# mcu.net
KiCad netlist of a schematic drawn in Altium Designer
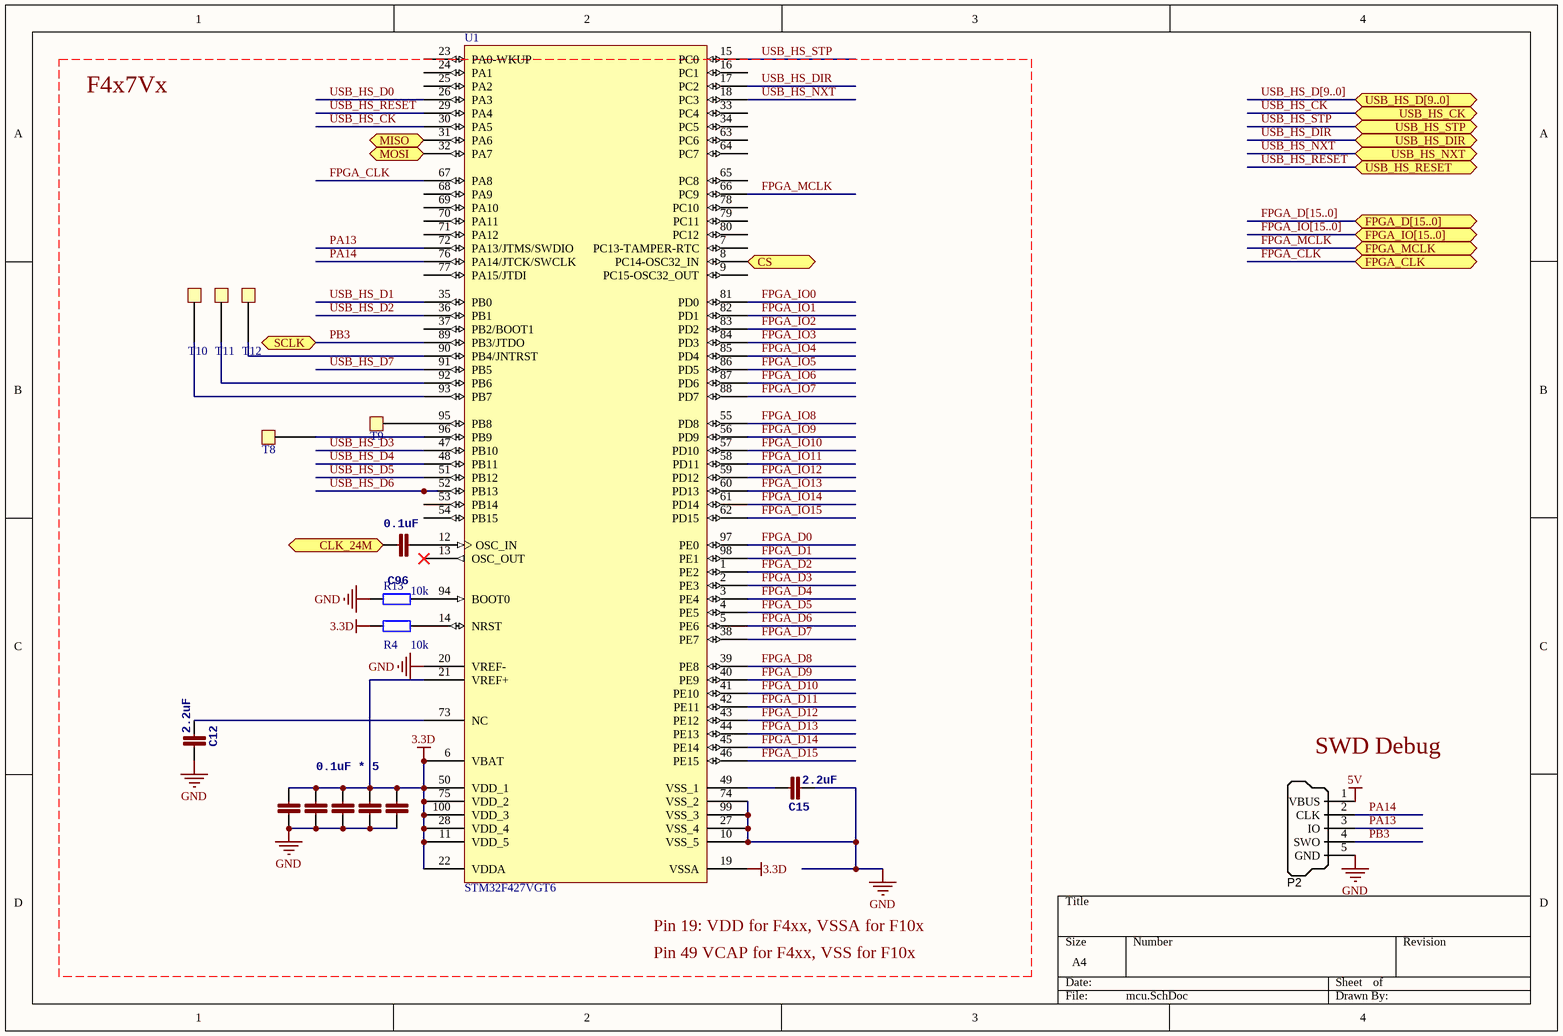
[diagram p0: mcu.SchDoc]

(export (version "E")
  (design (tool "Eeschema 10.0.6"))
  (components
    (comp (ref "C4")
      (value "0.1uF * 5")
      (footprint "0402")
      (description "<b>Capacitor</b>\nStandard 0603 ceramic capacitor, and 0.1\" leaded capacitor.")
      (fields (field (name "PARTNO") "CC0402ZRY5V7BB104"))
      (libsource (lib "*") (part "CAP0402-CAP"))
    )
    (comp (ref "C5")
      (value "1n")
      (footprint "0402")
      (description "<b>Capacitor</b>\nStandard 0603 ceramic capacitor, and 0.1\" leaded capacitor.")
      (fields (field (name "PARTNO") "CC0402ZRY5V7BB104"))
      (libsource (lib "") (part "CAP0402-CAP_1"))
    )
    (comp (ref "C6")
      (value "1n")
      (footprint "0402")
      (description "<b>Capacitor</b>\nStandard 0603 ceramic capacitor, and 0.1\" leaded capacitor.")
      (fields (field (name "PARTNO") "CC0402ZRY5V7BB104"))
      (libsource (lib "") (part "CAP0402-CAP_1"))
    )
    (comp (ref "C12")
      (value "2.2uF")
      (footprint "0603")
      (description "<b>Capacitor</b>\nStandard 0603 ceramic capacitor, and 0.1\" leaded capacitor.")
      (fields (field (name "PARTNO") "CC0402ZRY5V7BB104"))
      (libsource (lib "") (part "CAP0402-CAP_1"))
    )
    (comp (ref "C13")
      (value "1n")
      (footprint "0402")
      (description "<b>Capacitor</b>\nStandard 0603 ceramic capacitor, and 0.1\" leaded capacitor.")
      (fields (field (name "PARTNO") "CC0402ZRY5V7BB104"))
      (libsource (lib "") (part "CAP0402-CAP_1"))
    )
    (comp (ref "C14")
      (value "1n")
      (footprint "0402")
      (description "<b>Capacitor</b>\nStandard 0603 ceramic capacitor, and 0.1\" leaded capacitor.")
      (fields (field (name "PARTNO") "CC0402ZRY5V7BB104"))
      (libsource (lib "") (part "CAP0402-CAP_1"))
    )
    (comp (ref "C15")
      (value "2.2uF")
      (footprint "0603")
      (description "<b>Capacitor</b>\nStandard 0603 ceramic capacitor, and 0.1\" leaded capacitor.")
      (fields (field (name "PARTNO") "CC0402ZRY5V7BB104"))
      (libsource (lib "pixhawk2") (part "CAP0402-CAP"))
    )
    (comp (ref "C96")
      (value "0.1uF")
      (footprint "0402")
      (description "<b>Capacitor</b>\nStandard 0603 ceramic capacitor, and 0.1\" leaded capacitor.")
      (fields (field (name "PARTNO") "CC0402ZRY5V7BB104"))
      (libsource (lib "pixhawk2") (part "CAP0402-CAP"))
    )
    (comp (ref "P2")
      (value "SWD_MicroUSB")
      (footprint "MICRO-YZX")
      (description "Connector SMD USB Micro Type B middle mount")
      (libsource (lib "sch") (part "SWD_MicroUSB"))
    )
    (comp (ref "R4")
      (value "10k")
      (footprint "0402")
      (description "Resistor")
      (fields (field (name "PUBLISHER") "Altium Limited"))
      (libsource (lib "Miscellaneous Devices") (part "Res2"))
    )
    (comp (ref "R13")
      (value "10k")
      (footprint "0402")
      (description "Resistor")
      (fields (field (name "PUBLISHER") "Altium Limited"))
      (libsource (lib "") (part "Res2_1"))
    )
    (comp (ref "T8") (value "TestPad") (footprint "TestPad - 1mm") (libsource (lib "sch") (part "TestPad")))
    (comp (ref "T9") (value "TestPad") (footprint "TestPad - 1mm") (libsource (lib "sch") (part "TestPad")))
    (comp (ref "T10") (value "TestPad") (footprint "TestPad - 1mm") (libsource (lib "") (part "TestPad_1")))
    (comp (ref "T11") (value "TestPad") (footprint "TestPad - 1mm") (libsource (lib "") (part "TestPad_1")))
    (comp (ref "T12") (value "TestPad") (footprint "TestPad - 1mm") (libsource (lib "") (part "TestPad_1")))
    (comp (ref "U1")
      (value "STM32F427VGT6")
      (footprint "LQFP100_N")
      (description "STM32 ARM-based 32-bit MCU with 64 Kbytes Flash, 100-pin LQFP, Industrial Temperature")
      (fields (field (name "PUBLISHER") "*"))
      (libsource (lib "ST Microcontroller 32-Bit STM32 SCH") (part "STM32F103VBT6"))
    )
  )
  (nets
    (net (code "3") (name "/CLK_24M") (class "Default")
      (node (ref "C96") (pin "1") (pinfunction "1_1") (pintype "passive"))
    )
    (net (code "4") (name "/CS") (class "Default")
      (node (ref "U1") (pin "8") (pinfunction "PC14-OSC32_IN_8") (pintype "bidirectional"))
    )
    (net (code "5") (name "/FPGA_CLK") (class "Default")
      (node (ref "U1") (pin "67") (pinfunction "PA8_67") (pintype "bidirectional"))
    )
    (net (code "6") (name "/FPGA_D0") (class "Default")
      (node (ref "U1") (pin "97") (pinfunction "PE0_97") (pintype "bidirectional"))
    )
    (net (code "7") (name "/FPGA_D1") (class "Default")
      (node (ref "U1") (pin "98") (pinfunction "PE1_98") (pintype "bidirectional"))
    )
    (net (code "8") (name "/FPGA_D2") (class "Default")
      (node (ref "U1") (pin "1") (pinfunction "PE2_1") (pintype "bidirectional"))
    )
    (net (code "9") (name "/FPGA_D3") (class "Default")
      (node (ref "U1") (pin "2") (pinfunction "PE3_2") (pintype "bidirectional"))
    )
    (net (code "10") (name "/FPGA_D4") (class "Default")
      (node (ref "U1") (pin "3") (pinfunction "PE4_3") (pintype "bidirectional"))
    )
    (net (code "11") (name "/FPGA_D5") (class "Default")
      (node (ref "U1") (pin "4") (pinfunction "PE5_4") (pintype "bidirectional"))
    )
    (net (code "12") (name "/FPGA_D6") (class "Default")
      (node (ref "U1") (pin "5") (pinfunction "PE6_5") (pintype "bidirectional"))
    )
    (net (code "13") (name "/FPGA_D7") (class "Default")
      (node (ref "U1") (pin "38") (pinfunction "PE7_38") (pintype "bidirectional"))
    )
    (net (code "14") (name "/FPGA_D8") (class "Default")
      (node (ref "U1") (pin "39") (pinfunction "PE8_39") (pintype "bidirectional"))
    )
    (net (code "15") (name "/FPGA_D9") (class "Default")
      (node (ref "U1") (pin "40") (pinfunction "PE9_40") (pintype "bidirectional"))
    )
    (net (code "16") (name "/FPGA_D10") (class "Default")
      (node (ref "U1") (pin "41") (pinfunction "PE10_41") (pintype "bidirectional"))
    )
    (net (code "17") (name "/FPGA_D11") (class "Default")
      (node (ref "U1") (pin "42") (pinfunction "PE11_42") (pintype "bidirectional"))
    )
    (net (code "18") (name "/FPGA_D12") (class "Default")
      (node (ref "U1") (pin "43") (pinfunction "PE12_43") (pintype "bidirectional"))
    )
    (net (code "19") (name "/FPGA_D13") (class "Default")
      (node (ref "U1") (pin "44") (pinfunction "PE13_44") (pintype "bidirectional"))
    )
    (net (code "20") (name "/FPGA_D14") (class "Default")
      (node (ref "U1") (pin "45") (pinfunction "PE14_45") (pintype "bidirectional"))
    )
    (net (code "21") (name "/FPGA_D15") (class "Default")
      (node (ref "U1") (pin "46") (pinfunction "PE15_46") (pintype "bidirectional"))
    )
    (net (code "23") (name "/FPGA_IO0") (class "Default")
      (node (ref "U1") (pin "81") (pinfunction "PD0_81") (pintype "bidirectional"))
    )
    (net (code "24") (name "/FPGA_IO1") (class "Default")
      (node (ref "U1") (pin "82") (pinfunction "PD1_82") (pintype "bidirectional"))
    )
    (net (code "25") (name "/FPGA_IO2") (class "Default")
      (node (ref "U1") (pin "83") (pinfunction "PD2_83") (pintype "bidirectional"))
    )
    (net (code "26") (name "/FPGA_IO3") (class "Default")
      (node (ref "U1") (pin "84") (pinfunction "PD3_84") (pintype "bidirectional"))
    )
    (net (code "27") (name "/FPGA_IO4") (class "Default")
      (node (ref "U1") (pin "85") (pinfunction "PD4_85") (pintype "bidirectional"))
    )
    (net (code "28") (name "/FPGA_IO5") (class "Default")
      (node (ref "U1") (pin "86") (pinfunction "PD5_86") (pintype "bidirectional"))
    )
    (net (code "29") (name "/FPGA_IO6") (class "Default")
      (node (ref "U1") (pin "87") (pinfunction "PD6_87") (pintype "bidirectional"))
    )
    (net (code "30") (name "/FPGA_IO7") (class "Default")
      (node (ref "U1") (pin "88") (pinfunction "PD7_88") (pintype "bidirectional"))
    )
    (net (code "31") (name "/FPGA_IO8") (class "Default")
      (node (ref "U1") (pin "55") (pinfunction "PD8_55") (pintype "bidirectional"))
    )
    (net (code "32") (name "/FPGA_IO9") (class "Default")
      (node (ref "U1") (pin "56") (pinfunction "PD9_56") (pintype "bidirectional"))
    )
    (net (code "33") (name "/FPGA_IO10") (class "Default")
      (node (ref "U1") (pin "57") (pinfunction "PD10_57") (pintype "bidirectional"))
    )
    (net (code "34") (name "/FPGA_IO11") (class "Default")
      (node (ref "U1") (pin "58") (pinfunction "PD11_58") (pintype "bidirectional"))
    )
    (net (code "35") (name "/FPGA_IO12") (class "Default")
      (node (ref "U1") (pin "59") (pinfunction "PD12_59") (pintype "bidirectional"))
    )
    (net (code "36") (name "/FPGA_IO13") (class "Default")
      (node (ref "U1") (pin "60") (pinfunction "PD13_60") (pintype "bidirectional"))
    )
    (net (code "37") (name "/FPGA_IO14") (class "Default")
      (node (ref "U1") (pin "61") (pinfunction "PD14_61") (pintype "bidirectional"))
    )
    (net (code "38") (name "/FPGA_IO15") (class "Default")
      (node (ref "U1") (pin "62") (pinfunction "PD15_62") (pintype "bidirectional"))
    )
    (net (code "40") (name "/FPGA_MCLK") (class "Default")
      (node (ref "U1") (pin "66") (pinfunction "PC9_66") (pintype "bidirectional"))
    )
    (net (code "41") (name "/MISO") (class "Default")
      (node (ref "U1") (pin "31") (pinfunction "PA6_31") (pintype "bidirectional"))
    )
    (net (code "42") (name "/MOSI") (class "Default")
      (node (ref "U1") (pin "32") (pinfunction "PA7_32") (pintype "bidirectional"))
    )
    (net (code "43") (name "/PA13") (class "Default")
      (node (ref "P2") (pin "3") (pinfunction "IO_3") (pintype "passive"))
      (node (ref "U1") (pin "72") (pinfunction "PA13/JTMS/SWDIO_72") (pintype "bidirectional"))
    )
    (net (code "44") (name "/PA14") (class "Default")
      (node (ref "P2") (pin "2") (pinfunction "CLK_2") (pintype "passive"))
      (node (ref "U1") (pin "76") (pinfunction "PA14/JTCK/SWCLK_76") (pintype "bidirectional"))
    )
    (net (code "45") (name "/PB3") (class "Default")
      (node (ref "P2") (pin "4") (pinfunction "SWO_4") (pintype "passive"))
      (node (ref "U1") (pin "89") (pinfunction "PB3/JTDO_89") (pintype "bidirectional"))
    )
    (net (code "46") (name "/USB_HS_CK") (class "Default")
      (node (ref "U1") (pin "30") (pinfunction "PA5_30") (pintype "bidirectional"))
    )
    (net (code "47") (name "/USB_HS_D0") (class "Default")
      (node (ref "U1") (pin "26") (pinfunction "PA3_26") (pintype "bidirectional"))
    )
    (net (code "48") (name "/USB_HS_D1") (class "Default")
      (node (ref "U1") (pin "35") (pinfunction "PB0_35") (pintype "bidirectional"))
    )
    (net (code "49") (name "/USB_HS_D2") (class "Default")
      (node (ref "U1") (pin "36") (pinfunction "PB1_36") (pintype "bidirectional"))
    )
    (net (code "50") (name "/USB_HS_D3") (class "Default")
      (node (ref "U1") (pin "47") (pinfunction "PB10_47") (pintype "bidirectional"))
    )
    (net (code "51") (name "/USB_HS_D4") (class "Default")
      (node (ref "U1") (pin "48") (pinfunction "PB11_48") (pintype "bidirectional"))
    )
    (net (code "52") (name "/USB_HS_D5") (class "Default")
      (node (ref "U1") (pin "51") (pinfunction "PB12_51") (pintype "bidirectional"))
    )
    (net (code "53") (name "/USB_HS_D6") (class "Default")
      (node (ref "U1") (pin "52") (pinfunction "PB13_52") (pintype "bidirectional"))
    )
    (net (code "54") (name "/USB_HS_D7") (class "Default")
      (node (ref "U1") (pin "91") (pinfunction "PB5_91") (pintype "bidirectional"))
    )
    (net (code "55") (name "/USB_HS_DIR") (class "Default")
      (node (ref "U1") (pin "17") (pinfunction "PC2_17") (pintype "bidirectional"))
    )
    (net (code "57") (name "/USB_HS_NXT") (class "Default")
      (node (ref "U1") (pin "18") (pinfunction "PC3_18") (pintype "bidirectional"))
    )
    (net (code "58") (name "/USB_HS_RESET") (class "Default")
      (node (ref "U1") (pin "29") (pinfunction "PA4_29") (pintype "bidirectional"))
    )
    (net (code "59") (name "/USB_HS_STP") (class "Default")
      (node (ref "U1") (pin "15") (pinfunction "PC0_15") (pintype "bidirectional"))
    )
    (net (code "60") (name "3.3D") (class "Default")
      (node (ref "C13") (pin "2") (pinfunction "2_2") (pintype "passive"))
      (node (ref "C14") (pin "2") (pinfunction "2_2") (pintype "passive"))
      (node (ref "C4") (pin "2") (pinfunction "2_2") (pintype "passive"))
      (node (ref "C5") (pin "2") (pinfunction "2_2") (pintype "passive"))
      (node (ref "C6") (pin "2") (pinfunction "2_2") (pintype "passive"))
      (node (ref "R4") (pin "2") (pinfunction "2_2") (pintype "passive"))
      (node (ref "U1") (pin "100") (pinfunction "VDD_3_100") (pintype "power_in"))
      (node (ref "U1") (pin "11") (pinfunction "VDD_5_11") (pintype "power_in"))
      (node (ref "U1") (pin "19") (pinfunction "VSSA_19") (pintype "power_in"))
      (node (ref "U1") (pin "21") (pinfunction "VREF+_21") (pintype "power_in"))
      (node (ref "U1") (pin "22") (pinfunction "VDDA_22") (pintype "power_in"))
      (node (ref "U1") (pin "28") (pinfunction "VDD_4_28") (pintype "power_in"))
      (node (ref "U1") (pin "50") (pinfunction "VDD_1_50") (pintype "power_in"))
      (node (ref "U1") (pin "6") (pinfunction "VBAT_6") (pintype "power_in"))
      (node (ref "U1") (pin "75") (pinfunction "VDD_2_75") (pintype "power_in"))
    )
    (net (code "61") (name "5V") (class "Default")
      (node (ref "P2") (pin "1") (pinfunction "VBUS_1") (pintype "passive"))
    )
    (net (code "62") (name "GND") (class "Default")
      (node (ref "C12") (pin "1") (pinfunction "1_1") (pintype "passive"))
      (node (ref "C13") (pin "1") (pinfunction "1_1") (pintype "passive"))
      (node (ref "C14") (pin "1") (pinfunction "1_1") (pintype "passive"))
      (node (ref "C15") (pin "2") (pinfunction "2_2") (pintype "passive"))
      (node (ref "C4") (pin "1") (pinfunction "1_1") (pintype "passive"))
      (node (ref "C5") (pin "1") (pinfunction "1_1") (pintype "passive"))
      (node (ref "C6") (pin "1") (pinfunction "1_1") (pintype "passive"))
      (node (ref "P2") (pin "5") (pinfunction "GND_5") (pintype "passive"))
      (node (ref "R13") (pin "1") (pinfunction "1_1") (pintype "passive"))
      (node (ref "U1") (pin "10") (pinfunction "VSS_5_10") (pintype "power_in"))
      (node (ref "U1") (pin "20") (pinfunction "VREF-_20") (pintype "power_in"))
      (node (ref "U1") (pin "27") (pinfunction "VSS_4_27") (pintype "power_in"))
      (node (ref "U1") (pin "74") (pinfunction "VSS_2_74") (pintype "power_in"))
      (node (ref "U1") (pin "99") (pinfunction "VSS_3_99") (pintype "power_in"))
    )
    (net (code "63") (name "Net-(T8-3)") (class "Default")
      (node (ref "T8") (pin "1") (pinfunction "3_1") (pintype "passive"))
      (node (ref "U1") (pin "96") (pinfunction "PB9_96") (pintype "bidirectional"))
    )
    (net (code "64") (name "Net-(T9-3)") (class "Default")
      (node (ref "T9") (pin "1") (pinfunction "3_1") (pintype "passive"))
      (node (ref "U1") (pin "95") (pinfunction "PB8_95") (pintype "bidirectional"))
    )
    (net (code "65") (name "Net-(T10-3)") (class "Default")
      (node (ref "T10") (pin "1") (pinfunction "3_1") (pintype "passive"))
      (node (ref "U1") (pin "93") (pinfunction "PB7_93") (pintype "bidirectional"))
    )
    (net (code "66") (name "Net-(T11-3)") (class "Default")
      (node (ref "T11") (pin "1") (pinfunction "3_1") (pintype "passive"))
      (node (ref "U1") (pin "92") (pinfunction "PB6_92") (pintype "bidirectional"))
    )
    (net (code "67") (name "Net-(T12-3)") (class "Default")
      (node (ref "T12") (pin "1") (pinfunction "3_1") (pintype "passive"))
      (node (ref "U1") (pin "90") (pinfunction "PB4/JNTRST_90") (pintype "bidirectional"))
    )
    (net (code "68") (name "Net-(U1-BOOT0)") (class "Default")
      (node (ref "R13") (pin "2") (pinfunction "2_2") (pintype "passive"))
      (node (ref "U1") (pin "94") (pinfunction "BOOT0_94") (pintype "input"))
    )
    (net (code "69") (name "Net-(U1-NC)") (class "Default")
      (node (ref "C12") (pin "2") (pinfunction "2_2") (pintype "passive"))
      (node (ref "U1") (pin "73") (pinfunction "NC_73") (pintype "passive"))
    )
    (net (code "70") (name "Net-(U1-NRST)") (class "Default")
      (node (ref "R4") (pin "1") (pinfunction "1_1") (pintype "passive"))
      (node (ref "U1") (pin "14") (pinfunction "NRST_14") (pintype "bidirectional"))
    )
    (net (code "71") (name "Net-(U1-OSC_IN)") (class "Default")
      (node (ref "C96") (pin "2") (pinfunction "2_2") (pintype "passive"))
      (node (ref "U1") (pin "12") (pinfunction "OSC_IN_12") (pintype "input"))
    )
    (net (code "72") (name "Net-(U1-VSS_1)") (class "Default")
      (node (ref "C15") (pin "1") (pinfunction "1_1") (pintype "passive"))
      (node (ref "U1") (pin "49") (pinfunction "VSS_1_49") (pintype "power_in"))
    )
    (net (code "73") (name "unconnected-(U1-OSC_OUT-Pad13)") (class "Default")
      (node (ref "U1") (pin "13") (pinfunction "OSC_OUT_13") (pintype "output+no_connect"))
    )
    (net (code "74") (name "unconnected-(U1-PA0-WKUP-Pad23)") (class "Default")
      (node (ref "U1") (pin "23") (pinfunction "PA0-WKUP_23") (pintype "bidirectional"))
    )
    (net (code "75") (name "unconnected-(U1-PA1-Pad24)") (class "Default")
      (node (ref "U1") (pin "24") (pinfunction "PA1_24") (pintype "bidirectional"))
    )
    (net (code "76") (name "unconnected-(U1-PA2-Pad25)") (class "Default")
      (node (ref "U1") (pin "25") (pinfunction "PA2_25") (pintype "bidirectional"))
    )
    (net (code "77") (name "unconnected-(U1-PA9-Pad68)") (class "Default")
      (node (ref "U1") (pin "68") (pinfunction "PA9_68") (pintype "bidirectional"))
    )
    (net (code "78") (name "unconnected-(U1-PA10-Pad69)") (class "Default")
      (node (ref "U1") (pin "69") (pinfunction "PA10_69") (pintype "bidirectional"))
    )
    (net (code "79") (name "unconnected-(U1-PA11-Pad70)") (class "Default")
      (node (ref "U1") (pin "70") (pinfunction "PA11_70") (pintype "bidirectional"))
    )
    (net (code "80") (name "unconnected-(U1-PA12-Pad71)") (class "Default")
      (node (ref "U1") (pin "71") (pinfunction "PA12_71") (pintype "bidirectional"))
    )
    (net (code "81") (name "unconnected-(U1-PA15{slash}JTDI-Pad77)") (class "Default")
      (node (ref "U1") (pin "77") (pinfunction "PA15/JTDI_77") (pintype "bidirectional"))
    )
    (net (code "82") (name "unconnected-(U1-PB2{slash}BOOT1-Pad37)") (class "Default")
      (node (ref "U1") (pin "37") (pinfunction "PB2/BOOT1_37") (pintype "bidirectional"))
    )
    (net (code "83") (name "unconnected-(U1-PB14-Pad53)") (class "Default")
      (node (ref "U1") (pin "53") (pinfunction "PB14_53") (pintype "bidirectional"))
    )
    (net (code "84") (name "unconnected-(U1-PB15-Pad54)") (class "Default")
      (node (ref "U1") (pin "54") (pinfunction "PB15_54") (pintype "bidirectional"))
    )
    (net (code "85") (name "unconnected-(U1-PC1-Pad16)") (class "Default")
      (node (ref "U1") (pin "16") (pinfunction "PC1_16") (pintype "bidirectional"))
    )
    (net (code "86") (name "unconnected-(U1-PC4-Pad33)") (class "Default")
      (node (ref "U1") (pin "33") (pinfunction "PC4_33") (pintype "bidirectional"))
    )
    (net (code "87") (name "unconnected-(U1-PC5-Pad34)") (class "Default")
      (node (ref "U1") (pin "34") (pinfunction "PC5_34") (pintype "bidirectional"))
    )
    (net (code "88") (name "unconnected-(U1-PC6-Pad63)") (class "Default")
      (node (ref "U1") (pin "63") (pinfunction "PC6_63") (pintype "bidirectional"))
    )
    (net (code "89") (name "unconnected-(U1-PC7-Pad64)") (class "Default")
      (node (ref "U1") (pin "64") (pinfunction "PC7_64") (pintype "bidirectional"))
    )
    (net (code "90") (name "unconnected-(U1-PC8-Pad65)") (class "Default")
      (node (ref "U1") (pin "65") (pinfunction "PC8_65") (pintype "bidirectional"))
    )
    (net (code "91") (name "unconnected-(U1-PC10-Pad78)") (class "Default")
      (node (ref "U1") (pin "78") (pinfunction "PC10_78") (pintype "bidirectional"))
    )
    (net (code "92") (name "unconnected-(U1-PC11-Pad79)") (class "Default")
      (node (ref "U1") (pin "79") (pinfunction "PC11_79") (pintype "bidirectional"))
    )
    (net (code "93") (name "unconnected-(U1-PC12-Pad80)") (class "Default")
      (node (ref "U1") (pin "80") (pinfunction "PC12_80") (pintype "bidirectional"))
    )
    (net (code "94") (name "unconnected-(U1-PC13-TAMPER-RTC-Pad7)") (class "Default")
      (node (ref "U1") (pin "7") (pinfunction "PC13-TAMPER-RTC_7") (pintype "bidirectional"))
    )
    (net (code "95") (name "unconnected-(U1-PC15-OSC32_OUT-Pad9)") (class "Default")
      (node (ref "U1") (pin "9") (pinfunction "PC15-OSC32_OUT_9") (pintype "bidirectional"))
    )
  )
)
